# H01R0_Backend.net
KiCad netlist of a schematic drawn in Altium Designer
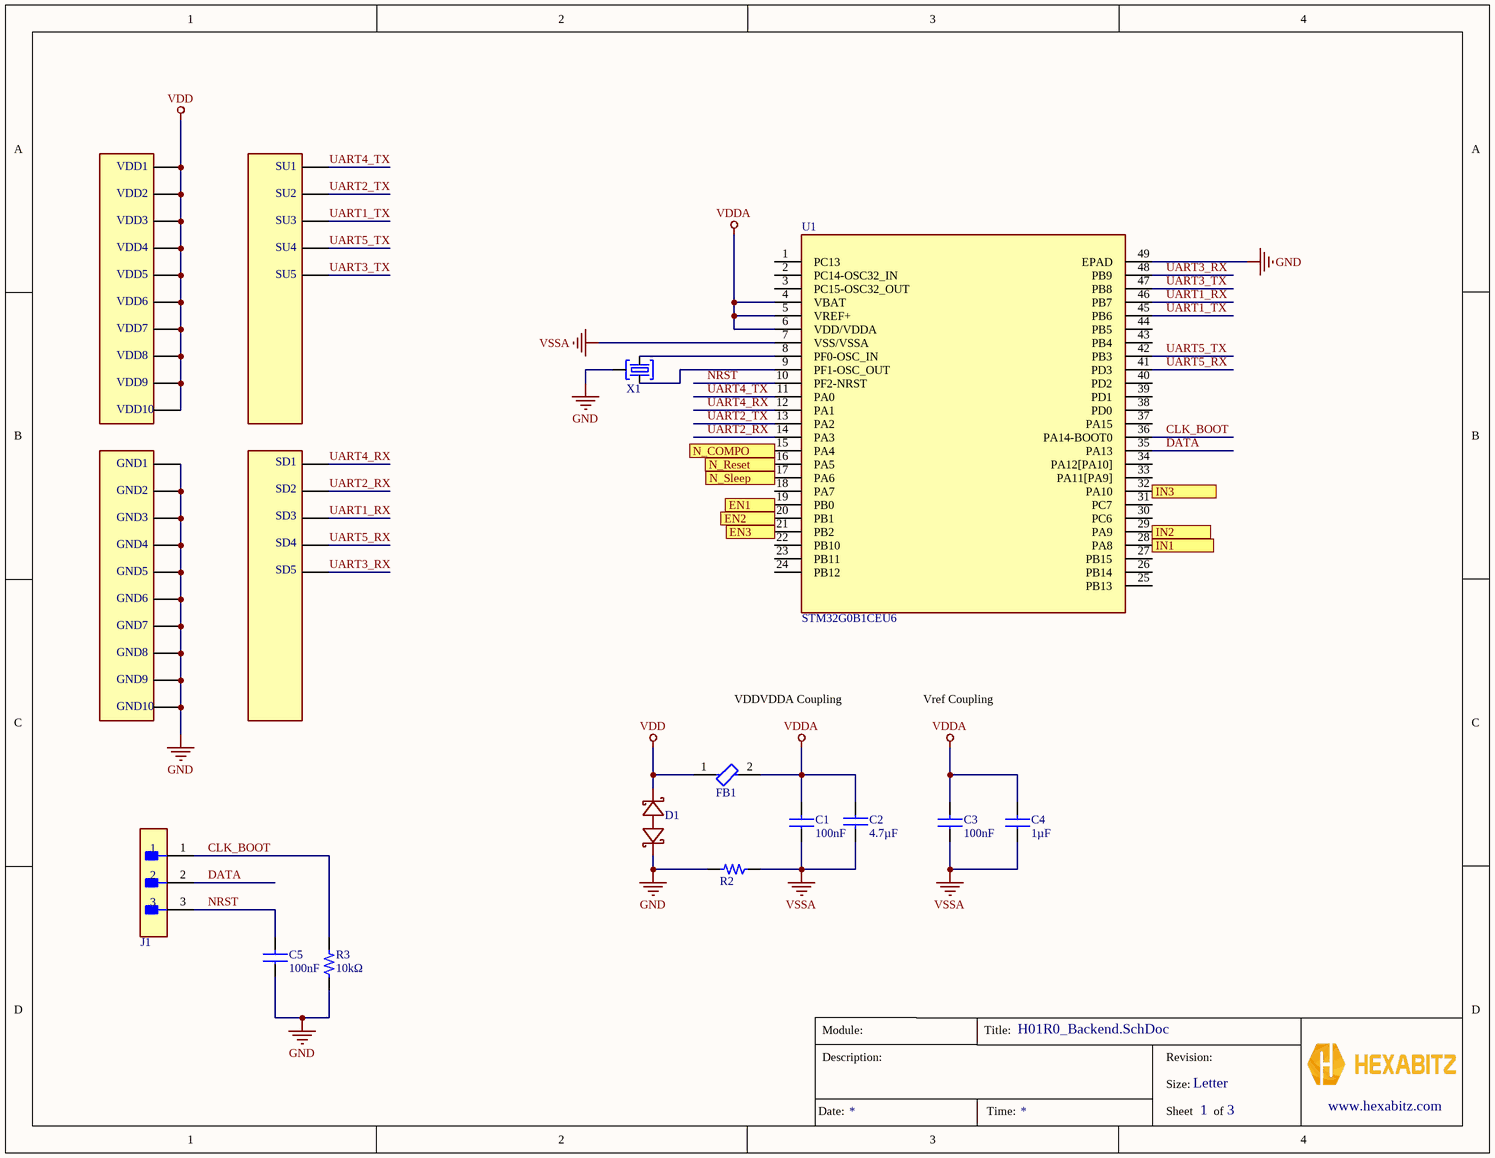
[diagram p0: H01R0_Backend.SchDoc]

(export (version "E")
  (design (tool "Eeschema 10.0.6"))
  (components
    (comp (ref "C1")
      (value "100nF")
      (footprint "C0603")
      (fields
        (field (name "MANUFACTURER") "Samsung Electro-Mechanics")
        (field (name "MANUFACTURER PART NUMBER") "CL10B104KA8NNNC")
        (field (name "TOLERANCE") "10%")
      )
      (libsource (lib "Hexabitz Altium Library") (part "generic Capacitor"))
    )
    (comp (ref "C2")
      (value "4.7µF")
      (footprint "C0805")
      (fields
        (field (name "MANUFACTURER") "Samsung Electro-Mechanics")
        (field (name "MANUFACTURER PART NUMBER") "CL21X475KAQNNNE")
        (field (name "TOLERANCE") "10%")
      )
      (libsource (lib "Hexabitz Altium Library") (part "generic Capacitor"))
    )
    (comp (ref "C3")
      (value "100nF")
      (footprint "C0603")
      (fields
        (field (name "MANUFACTURER") "Samsung Electro-Mechanics")
        (field (name "MANUFACTURER PART NUMBER") "CL10B104KA8NNNC")
        (field (name "TOLERANCE") "10%")
      )
      (libsource (lib "Hexabitz Altium Library") (part "generic Capacitor"))
    )
    (comp (ref "C4")
      (value "1µF")
      (footprint "C0805")
      (description "Ceramic Capacitor, Ceramic, 16V, 10% +Tol, 10% -Tol, X7R, 15% TC, 1uF, Surface Mount, 0805")
      (fields
        (field (name "MANUFACTURER") "Yageo Group")
        (field (name "MANUFACTURER PART NUMBER") "CC0805KKX7R7BB105")
      )
      (libsource (lib "Hexabitz Altium Library") (part "generic Capacitor"))
    )
    (comp (ref "C5")
      (value "100nF")
      (footprint "C0603")
      (fields
        (field (name "MANUFACTURER") "Samsung Electro-Mechanics")
        (field (name "MANUFACTURER PART NUMBER") "CL10B104KA8NNNC")
        (field (name "TOLERANCE") "10%")
      )
      (libsource (lib "Hexabitz Altium Library") (part "generic Capacitor"))
    )
    (comp (ref "D1")
      (value "CDSOD323-T03SC")
      (footprint "SOD2513X114N")
      (description "A 3V, 350W, bi-directional, standard capacitance, SOD323 pkg TVS Diode ¦ Bourns CDSOD323-T03SC")
      (fields (field (name "MANUFACTURER") "Bourns"))
      (libsource (lib "Hexabitz Altium Library") (part "CDSOD323-T03SC"))
    )
    (comp (ref "FB1")
      (value "MMZ1608Y300B")
      (footprint "FP-MMZ1608-0_8-MFG")
      (description "Ferrite Beads 0603 30ohms 1500mA Signal Line AEC-Q200")
      (fields
        (field (name "MANUFACTURER") "TDK")
        (field (name "MANUFACTURER PART NUMBER") "MMZ1608Y300BTD25")
      )
      (libsource (lib "Hexabitz Altium Library") (part "MMZ1608Y300B"))
    )
    (comp (ref "GND1")
      (value "HEXABIT_UART_PORT")
      (footprint "HEXABIT_POWER_PORT_D")
      (libsource (lib "hexabitz_connectors.Library") (part "HEXABIT_POWER_PORT_D"))
    )
    (comp (ref "GND2")
      (value "HEXABIT_UART_PORT")
      (footprint "HEXABIT_POWER_PORT_D")
      (libsource (lib "hexabitz_connectors.Library") (part "HEXABIT_POWER_PORT_D"))
    )
    (comp (ref "GND3")
      (value "HEXABIT_UART_PORT")
      (footprint "HEXABIT_POWER_PORT_D_300R")
      (libsource (lib "hexabitz_connectors.Library") (part "HEXABIT_POWER_PORT_D_300R"))
    )
    (comp (ref "GND4")
      (value "HEXABIT_UART_PORT")
      (footprint "HEXABIT_POWER_PORT_D")
      (libsource (lib "hexabitz_connectors.Library") (part "HEXABIT_POWER_PORT_D"))
    )
    (comp (ref "GND5")
      (value "HEXABIT_UART_PORT")
      (footprint "HEXABIT_POWER_PORT_D")
      (libsource (lib "hexabitz_connectors.Library") (part "HEXABIT_POWER_PORT_D"))
    )
    (comp (ref "GND6")
      (value "HEXABIT_UART_PORT")
      (footprint "HEXABIT_POWER_PORT_D")
      (libsource (lib "hexabitz_connectors.Library") (part "HEXABIT_POWER_PORT_D"))
    )
    (comp (ref "GND7")
      (value "HEXABIT_UART_PORT")
      (footprint "HEXABIT_POWER_PORT_D")
      (libsource (lib "hexabitz_connectors.Library") (part "HEXABIT_POWER_PORT_D"))
    )
    (comp (ref "GND8")
      (value "HEXABIT_UART_PORT")
      (footprint "HEXABIT_POWER_PORT_D_300L")
      (libsource (lib "hexabitz_connectors.Library") (part "HEXABIT_POWER_PORT_D_300L"))
    )
    (comp (ref "GND9")
      (value "HEXABIT_UART_PORT")
      (footprint "HEXABIT_POWER_PORT_D")
      (libsource (lib "hexabitz_connectors.Library") (part "HEXABIT_POWER_PORT_D"))
    )
    (comp (ref "GND10")
      (value "HEXABIT_UART_PORT")
      (footprint "HEXABIT_POWER_PORT_D")
      (libsource (lib "hexabitz_connectors.Library") (part "HEXABIT_POWER_PORT_D"))
    )
    (comp (ref "J1")
      (value "TSW-103-14-G-S")
      (footprint "FP-TSW-103-14-G-S-MFG")
      (description "CONN HEADER VERT 3POS 2.54MM")
      (libsource (lib "Altium Content Vault") (part "cd3439d6ef35ae5d9b27ec4fdd3e828"))
    )
    (comp (ref "R2")
      (value "Manufacturer Part Number")
      (footprint "R0603")
      (libsource (lib "") (part "generic Resistor_1"))
    )
    (comp (ref "R3")
      (value "10kΩ")
      (footprint "R0603")
      (description "100mW Thick Film Resistors ±100ppm/℃ ±1% 10kΩ 0603 Chip Resistor - Surface Mount ROHS")
      (fields
        (field (name "MANUFACTURER") "Yageo Group")
        (field (name "MANUFACTURER PART NUMBER") "RC0603FR-0710KL")
      )
      (libsource (lib "Hexabitz Altium Library") (part "generic Resistor"))
    )
    (comp (ref "SD1")
      (value "HEXABIT_UART_PORT")
      (footprint "HEXABIT_UART_PORT_D")
      (libsource (lib "hexabitz_connectors.Library") (part "HEXABIT_UART_PORT_D"))
    )
    (comp (ref "SD2")
      (value "HEXABIT_UART_PORT")
      (footprint "HEXABIT_UART_PORT_D")
      (libsource (lib "hexabitz_connectors.Library") (part "HEXABIT_UART_PORT_D"))
    )
    (comp (ref "SD3")
      (value "HEXABIT_UART_PORT")
      (footprint "HEXABIT_UART_PORT_D")
      (libsource (lib "hexabitz_connectors.Library") (part "HEXABIT_UART_PORT_D"))
    )
    (comp (ref "SD4")
      (value "HEXABIT_UART_PORT")
      (footprint "HEXABIT_UART_PORT_D")
      (libsource (lib "hexabitz_connectors.Library") (part "HEXABIT_UART_PORT_D"))
    )
    (comp (ref "SD5")
      (value "HEXABIT_UART_PORT")
      (footprint "HEXABIT_UART_PORT_D")
      (libsource (lib "hexabitz_connectors.Library") (part "HEXABIT_UART_PORT_D"))
    )
    (comp (ref "SU1")
      (value "HEXABIT_UART_PORT")
      (footprint "HEXABIT_UART_PORT_U")
      (libsource (lib "hexabitz_connectors.Library") (part "HEXABIT_UART_PORT_U"))
    )
    (comp (ref "SU2")
      (value "HEXABIT_UART_PORT")
      (footprint "HEXABIT_UART_PORT_U")
      (libsource (lib "hexabitz_connectors.Library") (part "HEXABIT_UART_PORT_U"))
    )
    (comp (ref "SU3")
      (value "HEXABIT_UART_PORT")
      (footprint "HEXABIT_UART_PORT_U")
      (libsource (lib "hexabitz_connectors.Library") (part "HEXABIT_UART_PORT_U"))
    )
    (comp (ref "SU4")
      (value "HEXABIT_UART_PORT")
      (footprint "HEXABIT_UART_PORT_U")
      (libsource (lib "hexabitz_connectors.Library") (part "HEXABIT_UART_PORT_U"))
    )
    (comp (ref "SU5")
      (value "HEXABIT_UART_PORT")
      (footprint "HEXABIT_UART_PORT_U")
      (libsource (lib "hexabitz_connectors.Library") (part "HEXABIT_UART_PORT_U"))
    )
    (comp (ref "U1")
      (value "STM32G0B1CEU6")
      (footprint "QFN50P700X700X65-49N-D")
      (description "MCU 32-bit ARM Cortex M0+ RISC 512KB Flash 1.8V/2.5V/3.3V 48-Pin UFQFPN EP Tray")
      (fields
        (field (name "MANUFACTURER") "STMicroelectronics")
        (field (name "MANUFACTURER PART NUMBER") "STM32G0B1CEU6")
      )
      (libsource (lib "Hexabitz Altium Library") (part "STM32G0B1CEU6"))
    )
    (comp (ref "VDD1")
      (value "HEXABIT_UART_PORT")
      (footprint "HEXABIT_POWER_PORT_U")
      (libsource (lib "hexabitz_connectors.Library") (part "HEXABIT_POWER_PORT_U"))
    )
    (comp (ref "VDD2")
      (value "HEXABIT_UART_PORT")
      (footprint "HEXABIT_POWER_PORT_U")
      (libsource (lib "hexabitz_connectors.Library") (part "HEXABIT_POWER_PORT_U"))
    )
    (comp (ref "VDD3")
      (value "HEXABIT_UART_PORT")
      (footprint "HEXABIT_POWER_PORT_U_300R")
      (libsource (lib "hexabitz_connectors.Library") (part "HEXABIT_POWER_PORT_U_300R"))
    )
    (comp (ref "VDD4")
      (value "HEXABIT_UART_PORT")
      (footprint "HEXABIT_POWER_PORT_U")
      (libsource (lib "hexabitz_connectors.Library") (part "HEXABIT_POWER_PORT_U"))
    )
    (comp (ref "VDD5")
      (value "HEXABIT_UART_PORT")
      (footprint "HEXABIT_POWER_PORT_U")
      (libsource (lib "hexabitz_connectors.Library") (part "HEXABIT_POWER_PORT_U"))
    )
    (comp (ref "VDD6")
      (value "HEXABIT_UART_PORT")
      (footprint "HEXABIT_POWER_PORT_U")
      (libsource (lib "hexabitz_connectors.Library") (part "HEXABIT_POWER_PORT_U"))
    )
    (comp (ref "VDD7")
      (value "HEXABIT_UART_PORT")
      (footprint "HEXABIT_POWER_PORT_U")
      (libsource (lib "hexabitz_connectors.Library") (part "HEXABIT_POWER_PORT_U"))
    )
    (comp (ref "VDD8")
      (value "HEXABIT_UART_PORT")
      (footprint "HEXABIT_POWER_PORT_U_300L")
      (libsource (lib "hexabitz_connectors.Library") (part "HEXABIT_POWER_PORT_U_300L"))
    )
    (comp (ref "VDD9")
      (value "HEXABIT_UART_PORT")
      (footprint "HEXABIT_POWER_PORT_U")
      (libsource (lib "hexabitz_connectors.Library") (part "HEXABIT_POWER_PORT_U"))
    )
    (comp (ref "VDD10")
      (value "HEXABIT_UART_PORT")
      (footprint "HEXABIT_POWER_PORT_U")
      (libsource (lib "hexabitz_connectors.Library") (part "HEXABIT_POWER_PORT_U"))
    )
    (comp (ref "X1")
      (value "CSTCE8M00G52Z-R0")
      (footprint "XTALL_CSTCE8M00G52")
      (description "Ceramic Resonator 8MHz ±0.5% (Tol) ±0.2% (Stability) 10pF 40Ohm 3-Pin CSMD T/R")
      (fields (field (name "MANUFACTURER") "Murata") (field (name "TOLERANCE") "0.5%"))
      (libsource (lib "Hexabitz Altium Library") (part "CSTCE8M00G52Z-R0"))
    )
  )
  (nets
    (net (code "1") (name "/CLK_BOOT") (class "Default")
      (node (ref "J1") (pin "1") (pinfunction "1_1") (pintype "passive"))
      (node (ref "R3") (pin "1") (pinfunction "1_1") (pintype "passive"))
      (node (ref "U1") (pin "36") (pinfunction "PA14-BOOT0_36") (pintype "passive"))
    )
    (net (code "2") (name "/DATA") (class "Default")
      (node (ref "J1") (pin "2") (pinfunction "2_2") (pintype "passive"))
      (node (ref "U1") (pin "35") (pinfunction "PA13_35") (pintype "passive"))
    )
    (net (code "3") (name "/EN1") (class "Default")
      (node (ref "U1") (pin "19") (pinfunction "PB0_19") (pintype "passive"))
    )
    (net (code "4") (name "/EN2") (class "Default")
      (node (ref "U1") (pin "20") (pinfunction "PB1_20") (pintype "passive"))
    )
    (net (code "5") (name "/EN3") (class "Default")
      (node (ref "U1") (pin "21") (pinfunction "PB2_21") (pintype "passive"))
    )
    (net (code "6") (name "/IN1") (class "Default")
      (node (ref "U1") (pin "28") (pinfunction "PA8_28") (pintype "passive"))
    )
    (net (code "7") (name "/IN2") (class "Default")
      (node (ref "U1") (pin "29") (pinfunction "PA9_29") (pintype "passive"))
    )
    (net (code "8") (name "/IN3") (class "Default")
      (node (ref "U1") (pin "32") (pinfunction "PA10_32") (pintype "passive"))
    )
    (net (code "9") (name "/NRST") (class "Default")
      (node (ref "C5") (pin "2") (pinfunction "2_2") (pintype "passive"))
      (node (ref "J1") (pin "3") (pinfunction "3_3") (pintype "passive"))
      (node (ref "U1") (pin "10") (pinfunction "PF2-NRST_10") (pintype "passive"))
    )
    (net (code "10") (name "/N_COMPO") (class "Default")
      (node (ref "U1") (pin "15") (pinfunction "PA4_15") (pintype "passive"))
    )
    (net (code "11") (name "/N_Reset") (class "Default")
      (node (ref "U1") (pin "16") (pinfunction "PA5_16") (pintype "passive"))
    )
    (net (code "12") (name "/N_Sleep") (class "Default")
      (node (ref "U1") (pin "17") (pinfunction "PA6_17") (pintype "passive"))
    )
    (net (code "13") (name "/UART1_RX") (class "Default")
      (node (ref "SD3") (pin "UART_D") (pinfunction "UART_D_UART_D") (pintype "passive"))
      (node (ref "U1") (pin "46") (pinfunction "PB7_46") (pintype "passive"))
    )
    (net (code "14") (name "/UART1_TX") (class "Default")
      (node (ref "SU3") (pin "UART_U") (pinfunction "UART_U_UART_U") (pintype "passive"))
      (node (ref "U1") (pin "45") (pinfunction "PB6_45") (pintype "passive"))
    )
    (net (code "15") (name "/UART2_RX") (class "Default")
      (node (ref "SD2") (pin "UART_D") (pinfunction "UART_D_UART_D") (pintype "passive"))
      (node (ref "U1") (pin "14") (pinfunction "PA3_14") (pintype "passive"))
    )
    (net (code "16") (name "/UART2_TX") (class "Default")
      (node (ref "SU2") (pin "UART_U") (pinfunction "UART_U_UART_U") (pintype "passive"))
      (node (ref "U1") (pin "13") (pinfunction "PA2_13") (pintype "passive"))
    )
    (net (code "17") (name "/UART3_RX") (class "Default")
      (node (ref "SD5") (pin "UART_D") (pinfunction "UART_D_UART_D") (pintype "passive"))
      (node (ref "U1") (pin "48") (pinfunction "PB9_48") (pintype "passive"))
    )
    (net (code "18") (name "/UART3_TX") (class "Default")
      (node (ref "SU5") (pin "UART_U") (pinfunction "UART_U_UART_U") (pintype "passive"))
      (node (ref "U1") (pin "47") (pinfunction "PB8_47") (pintype "passive"))
    )
    (net (code "19") (name "/UART4_RX") (class "Default")
      (node (ref "SD1") (pin "UART_D") (pinfunction "UART_D_UART_D") (pintype "passive"))
      (node (ref "U1") (pin "12") (pinfunction "PA1_12") (pintype "passive"))
    )
    (net (code "20") (name "/UART4_TX") (class "Default")
      (node (ref "SU1") (pin "UART_U") (pinfunction "UART_U_UART_U") (pintype "passive"))
      (node (ref "U1") (pin "11") (pinfunction "PA0_11") (pintype "passive"))
    )
    (net (code "21") (name "/UART5_RX") (class "Default")
      (node (ref "SD4") (pin "UART_D") (pinfunction "UART_D_UART_D") (pintype "passive"))
      (node (ref "U1") (pin "41") (pinfunction "PD3_41") (pintype "passive"))
    )
    (net (code "22") (name "/UART5_TX") (class "Default")
      (node (ref "SU4") (pin "UART_U") (pinfunction "UART_U_UART_U") (pintype "passive"))
      (node (ref "U1") (pin "42") (pinfunction "PB3_42") (pintype "passive"))
    )
    (net (code "23") (name "GND") (class "Default")
      (node (ref "C5") (pin "1") (pinfunction "1_1") (pintype "passive"))
      (node (ref "D1") (pin "1") (pinfunction "A_1") (pintype "passive"))
      (node (ref "GND1") (pin "Pwr_D") (pinfunction "Pwr_D_Pwr_D") (pintype "passive"))
      (node (ref "GND10") (pin "Pwr_D") (pinfunction "Pwr_D_Pwr_D") (pintype "passive"))
      (node (ref "GND2") (pin "Pwr_D") (pinfunction "Pwr_D_Pwr_D") (pintype "passive"))
      (node (ref "GND3") (pin "Pwr_D") (pinfunction "Pwr_D_Pwr_D") (pintype "passive"))
      (node (ref "GND4") (pin "Pwr_D") (pinfunction "Pwr_D_Pwr_D") (pintype "passive"))
      (node (ref "GND5") (pin "Pwr_D") (pinfunction "Pwr_D_Pwr_D") (pintype "passive"))
      (node (ref "GND6") (pin "Pwr_D") (pinfunction "Pwr_D_Pwr_D") (pintype "passive"))
      (node (ref "GND7") (pin "Pwr_D") (pinfunction "Pwr_D_Pwr_D") (pintype "passive"))
      (node (ref "GND8") (pin "Pwr_D") (pinfunction "Pwr_D_Pwr_D") (pintype "passive"))
      (node (ref "GND9") (pin "Pwr_D") (pinfunction "Pwr_D_Pwr_D") (pintype "passive"))
      (node (ref "R2") (pin "1") (pinfunction "1_1") (pintype "passive"))
      (node (ref "R3") (pin "2") (pinfunction "2_2") (pintype "passive"))
      (node (ref "U1") (pin "49") (pinfunction "EPAD_49") (pintype "passive"))
      (node (ref "X1") (pin "P$2") (pinfunction "2_P$2") (pintype "passive"))
    )
    (net (code "24") (name "Net-(U1-PF0-OSC_IN)") (class "Default")
      (node (ref "U1") (pin "8") (pinfunction "PF0-OSC_IN_8") (pintype "passive"))
      (node (ref "X1") (pin "P$3") (pinfunction "3_P$3") (pintype "passive"))
    )
    (net (code "25") (name "Net-(U1-PF1-OSC_OUT)") (class "Default")
      (node (ref "U1") (pin "9") (pinfunction "PF1-OSC_OUT_9") (pintype "passive"))
      (node (ref "X1") (pin "P$1") (pinfunction "1_P$1") (pintype "passive"))
    )
    (net (code "26") (name "VDD") (class "Default")
      (node (ref "D1") (pin "2") (pinfunction "C_2") (pintype "passive"))
      (node (ref "FB1") (pin "1") (pinfunction "1_1") (pintype "passive"))
      (node (ref "VDD1") (pin "Pwr_U") (pinfunction "Pwr_U_Pwr_U") (pintype "passive"))
      (node (ref "VDD10") (pin "Pwr_U") (pinfunction "Pwr_U_Pwr_U") (pintype "passive"))
      (node (ref "VDD2") (pin "Pwr_U") (pinfunction "Pwr_U_Pwr_U") (pintype "passive"))
      (node (ref "VDD3") (pin "Pwr_U") (pinfunction "Pwr_U_Pwr_U") (pintype "passive"))
      (node (ref "VDD4") (pin "Pwr_U") (pinfunction "Pwr_U_Pwr_U") (pintype "passive"))
      (node (ref "VDD5") (pin "Pwr_U") (pinfunction "Pwr_U_Pwr_U") (pintype "passive"))
      (node (ref "VDD6") (pin "Pwr_U") (pinfunction "Pwr_U_Pwr_U") (pintype "passive"))
      (node (ref "VDD7") (pin "Pwr_U") (pinfunction "Pwr_U_Pwr_U") (pintype "passive"))
      (node (ref "VDD8") (pin "Pwr_U") (pinfunction "Pwr_U_Pwr_U") (pintype "passive"))
      (node (ref "VDD9") (pin "Pwr_U") (pinfunction "Pwr_U_Pwr_U") (pintype "passive"))
    )
    (net (code "27") (name "VDDA") (class "Default")
      (node (ref "C1") (pin "2") (pinfunction "2_2") (pintype "passive"))
      (node (ref "C2") (pin "1") (pinfunction "1_1") (pintype "passive"))
      (node (ref "C3") (pin "2") (pinfunction "2_2") (pintype "passive"))
      (node (ref "C4") (pin "2") (pinfunction "2_2") (pintype "passive"))
      (node (ref "FB1") (pin "2") (pinfunction "2_2") (pintype "passive"))
      (node (ref "U1") (pin "4") (pinfunction "VBAT_4") (pintype "passive"))
      (node (ref "U1") (pin "5") (pinfunction "VREF+_5") (pintype "passive"))
      (node (ref "U1") (pin "6") (pinfunction "VDD/VDDA_6") (pintype "passive"))
    )
    (net (code "28") (name "VSSA") (class "Default")
      (node (ref "C1") (pin "1") (pinfunction "1_1") (pintype "passive"))
      (node (ref "C2") (pin "2") (pinfunction "2_2") (pintype "passive"))
      (node (ref "C3") (pin "1") (pinfunction "1_1") (pintype "passive"))
      (node (ref "C4") (pin "1") (pinfunction "1_1") (pintype "passive"))
      (node (ref "R2") (pin "2") (pinfunction "2_2") (pintype "passive"))
      (node (ref "U1") (pin "7") (pinfunction "VSS/VSSA_7") (pintype "passive"))
    )
    (net (code "29") (name "unconnected-(U1-PA7-Pad18)") (class "Default")
      (node (ref "U1") (pin "18") (pinfunction "PA7_18") (pintype "passive"))
    )
    (net (code "30") (name "unconnected-(U1-PA11[PA9]-Pad33)") (class "Default")
      (node (ref "U1") (pin "33") (pinfunction "PA11[PA9]_33") (pintype "passive"))
    )
    (net (code "31") (name "unconnected-(U1-PA12[PA10]-Pad34)") (class "Default")
      (node (ref "U1") (pin "34") (pinfunction "PA12[PA10]_34") (pintype "passive"))
    )
    (net (code "32") (name "unconnected-(U1-PA15-Pad37)") (class "Default")
      (node (ref "U1") (pin "37") (pinfunction "PA15_37") (pintype "passive"))
    )
    (net (code "33") (name "unconnected-(U1-PB4-Pad43)") (class "Default")
      (node (ref "U1") (pin "43") (pinfunction "PB4_43") (pintype "passive"))
    )
    (net (code "34") (name "unconnected-(U1-PB5-Pad44)") (class "Default")
      (node (ref "U1") (pin "44") (pinfunction "PB5_44") (pintype "passive"))
    )
    (net (code "35") (name "unconnected-(U1-PB10-Pad22)") (class "Default")
      (node (ref "U1") (pin "22") (pinfunction "PB10_22") (pintype "passive"))
    )
    (net (code "36") (name "unconnected-(U1-PB11-Pad23)") (class "Default")
      (node (ref "U1") (pin "23") (pinfunction "PB11_23") (pintype "passive"))
    )
    (net (code "37") (name "unconnected-(U1-PB12-Pad24)") (class "Default")
      (node (ref "U1") (pin "24") (pinfunction "PB12_24") (pintype "passive"))
    )
    (net (code "38") (name "unconnected-(U1-PB13-Pad25)") (class "Default")
      (node (ref "U1") (pin "25") (pinfunction "PB13_25") (pintype "passive"))
    )
    (net (code "39") (name "unconnected-(U1-PB14-Pad26)") (class "Default")
      (node (ref "U1") (pin "26") (pinfunction "PB14_26") (pintype "passive"))
    )
    (net (code "40") (name "unconnected-(U1-PB15-Pad27)") (class "Default")
      (node (ref "U1") (pin "27") (pinfunction "PB15_27") (pintype "passive"))
    )
    (net (code "41") (name "unconnected-(U1-PC6-Pad30)") (class "Default")
      (node (ref "U1") (pin "30") (pinfunction "PC6_30") (pintype "passive"))
    )
    (net (code "42") (name "unconnected-(U1-PC7-Pad31)") (class "Default")
      (node (ref "U1") (pin "31") (pinfunction "PC7_31") (pintype "passive"))
    )
    (net (code "43") (name "unconnected-(U1-PC13-Pad1)") (class "Default")
      (node (ref "U1") (pin "1") (pinfunction "PC13_1") (pintype "passive"))
    )
    (net (code "44") (name "unconnected-(U1-PC14-OSC32_IN-Pad2)") (class "Default")
      (node (ref "U1") (pin "2") (pinfunction "PC14-OSC32_IN_2") (pintype "passive"))
    )
    (net (code "45") (name "unconnected-(U1-PC15-OSC32_OUT-Pad3)") (class "Default")
      (node (ref "U1") (pin "3") (pinfunction "PC15-OSC32_OUT_3") (pintype "passive"))
    )
    (net (code "46") (name "unconnected-(U1-PD0-Pad38)") (class "Default")
      (node (ref "U1") (pin "38") (pinfunction "PD0_38") (pintype "passive"))
    )
    (net (code "47") (name "unconnected-(U1-PD1-Pad39)") (class "Default")
      (node (ref "U1") (pin "39") (pinfunction "PD1_39") (pintype "passive"))
    )
    (net (code "48") (name "unconnected-(U1-PD2-Pad40)") (class "Default")
      (node (ref "U1") (pin "40") (pinfunction "PD2_40") (pintype "passive"))
    )
  )
)
